# Clock_circuit.net
KiCad netlist of a schematic drawn in Altium Designer
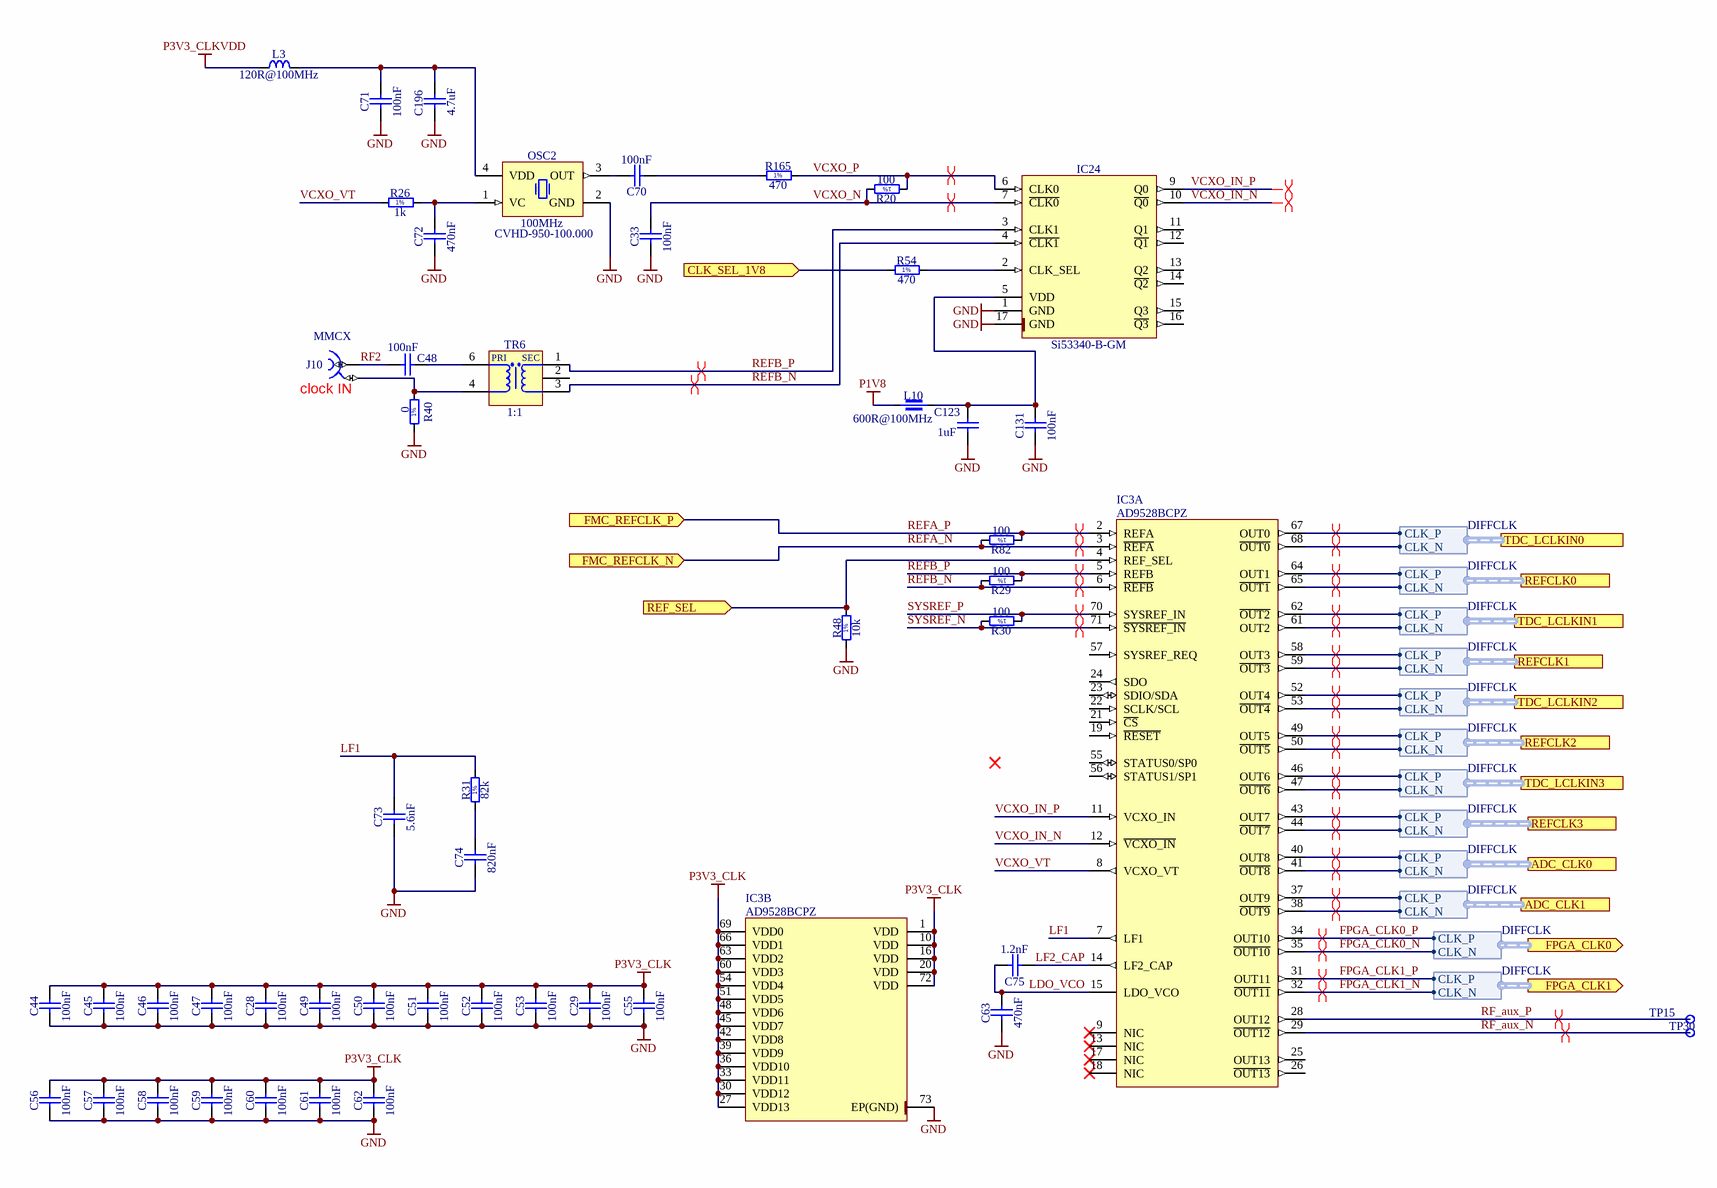
[diagram p0: Clock_circuit.SchDoc]

(export (version "E")
  (design (tool "Eeschema 10.0.6"))
  (components
    (comp (ref "C28")
      (value "100nF")
      (footprint "CAPC0603X33N")
      (description "Non-polarised capacitor")
      (fields
        (field (name "TOLERANCE") "±10%")
        (field (name "PART NUMBER") "CC0201_100NF_6.3V_10%_X5R")
        (field (name "AUTHOR") "CERN DEM JLC")
      )
      (libsource (lib "Capacitors") (part "Capacitor - non polarized"))
    )
    (comp (ref "C29")
      (value "100nF")
      (footprint "CAPC0603X33N")
      (description "Non-polarised capacitor")
      (fields
        (field (name "TOLERANCE") "±10%")
        (field (name "PART NUMBER") "CC0201_100NF_6.3V_10%_X5R")
        (field (name "AUTHOR") "CERN DEM JLC")
      )
      (libsource (lib "Capacitors") (part "Capacitor - non polarized"))
    )
    (comp (ref "C33")
      (value "100nF")
      (footprint "CAPC0603X33N")
      (description "Non-polarised capacitor")
      (fields
        (field (name "TOLERANCE") "±10%")
        (field (name "PART NUMBER") "CC0201_100NF_6.3V_10%_X5R")
        (field (name "AUTHOR") "CERN DEM JLC")
      )
      (libsource (lib "Capacitors") (part "Capacitor - non polarized"))
    )
    (comp (ref "C44")
      (value "100nF")
      (footprint "CAPC0603X33N")
      (description "Non-polarised capacitor")
      (fields
        (field (name "TOLERANCE") "±10%")
        (field (name "PART NUMBER") "CC0201_100NF_6.3V_10%_X5R")
        (field (name "AUTHOR") "CERN DEM JLC")
      )
      (libsource (lib "Capacitors") (part "Capacitor - non polarized"))
    )
    (comp (ref "C45")
      (value "100nF")
      (footprint "CAPC0603X33N")
      (description "Non-polarised capacitor")
      (fields
        (field (name "TOLERANCE") "±10%")
        (field (name "PART NUMBER") "CC0201_100NF_6.3V_10%_X5R")
        (field (name "AUTHOR") "CERN DEM JLC")
      )
      (libsource (lib "Capacitors") (part "Capacitor - non polarized"))
    )
    (comp (ref "C46")
      (value "100nF")
      (footprint "CAPC0603X33N")
      (description "Non-polarised capacitor")
      (fields
        (field (name "TOLERANCE") "±10%")
        (field (name "PART NUMBER") "CC0201_100NF_6.3V_10%_X5R")
        (field (name "AUTHOR") "CERN DEM JLC")
      )
      (libsource (lib "Capacitors") (part "Capacitor - non polarized"))
    )
    (comp (ref "C47")
      (value "100nF")
      (footprint "CAPC0603X33N")
      (description "Non-polarised capacitor")
      (fields
        (field (name "TOLERANCE") "±10%")
        (field (name "PART NUMBER") "CC0201_100NF_6.3V_10%_X5R")
        (field (name "AUTHOR") "CERN DEM JLC")
      )
      (libsource (lib "Capacitors") (part "Capacitor - non polarized"))
    )
    (comp (ref "C48")
      (value "100nF")
      (footprint "CAPC0603X33N")
      (description "Non-polarised capacitor")
      (fields
        (field (name "PART NUMBER") "CC0201_100NF_6.3V_10%_X5R")
        (field (name "VOLTAGE") "6.3V")
        (field (name "AUTHOR") "CERN DEM JLC")
      )
      (libsource (lib "Capacitors") (part "Capacitor - non polarized"))
    )
    (comp (ref "C49")
      (value "100nF")
      (footprint "CAPC0603X33N")
      (description "Non-polarised capacitor")
      (fields
        (field (name "TOLERANCE") "±10%")
        (field (name "PART NUMBER") "CC0201_100NF_6.3V_10%_X5R")
        (field (name "AUTHOR") "CERN DEM JLC")
      )
      (libsource (lib "Capacitors") (part "Capacitor - non polarized"))
    )
    (comp (ref "C50")
      (value "100nF")
      (footprint "CAPC0603X33N")
      (description "Non-polarised capacitor")
      (fields
        (field (name "TOLERANCE") "±10%")
        (field (name "PART NUMBER") "CC0201_100NF_6.3V_10%_X5R")
        (field (name "AUTHOR") "CERN DEM JLC")
      )
      (libsource (lib "Capacitors") (part "Capacitor - non polarized"))
    )
    (comp (ref "C51")
      (value "100nF")
      (footprint "CAPC0603X33N")
      (description "Non-polarised capacitor")
      (fields
        (field (name "TOLERANCE") "±10%")
        (field (name "PART NUMBER") "CC0201_100NF_6.3V_10%_X5R")
        (field (name "AUTHOR") "CERN DEM JLC")
      )
      (libsource (lib "Capacitors") (part "Capacitor - non polarized"))
    )
    (comp (ref "C52")
      (value "100nF")
      (footprint "CAPC0603X33N")
      (description "Non-polarised capacitor")
      (fields
        (field (name "TOLERANCE") "±10%")
        (field (name "PART NUMBER") "CC0201_100NF_6.3V_10%_X5R")
        (field (name "AUTHOR") "CERN DEM JLC")
      )
      (libsource (lib "Capacitors") (part "Capacitor - non polarized"))
    )
    (comp (ref "C53")
      (value "100nF")
      (footprint "CAPC0603X33N")
      (description "Non-polarised capacitor")
      (fields
        (field (name "TOLERANCE") "±10%")
        (field (name "PART NUMBER") "CC0201_100NF_6.3V_10%_X5R")
        (field (name "AUTHOR") "CERN DEM JLC")
      )
      (libsource (lib "Capacitors") (part "Capacitor - non polarized"))
    )
    (comp (ref "C55")
      (value "100nF")
      (footprint "CAPC0603X33N")
      (description "Non-polarised capacitor")
      (fields
        (field (name "TOLERANCE") "±10%")
        (field (name "PART NUMBER") "CC0201_100NF_6.3V_10%_X5R")
        (field (name "AUTHOR") "CERN DEM JLC")
      )
      (libsource (lib "Capacitors") (part "Capacitor - non polarized"))
    )
    (comp (ref "C56")
      (value "100nF")
      (footprint "CAPC0603X33N")
      (description "Non-polarised capacitor")
      (fields
        (field (name "TOLERANCE") "±10%")
        (field (name "PART NUMBER") "CC0201_100NF_6.3V_10%_X5R")
        (field (name "AUTHOR") "CERN DEM JLC")
      )
      (libsource (lib "Capacitors") (part "Capacitor - non polarized"))
    )
    (comp (ref "C57")
      (value "100nF")
      (footprint "CAPC0603X33N")
      (description "Non-polarised capacitor")
      (fields
        (field (name "TOLERANCE") "±10%")
        (field (name "PART NUMBER") "CC0201_100NF_6.3V_10%_X5R")
        (field (name "AUTHOR") "CERN DEM JLC")
      )
      (libsource (lib "Capacitors") (part "Capacitor - non polarized"))
    )
    (comp (ref "C58")
      (value "100nF")
      (footprint "CAPC0603X33N")
      (description "Non-polarised capacitor")
      (fields
        (field (name "TOLERANCE") "±10%")
        (field (name "PART NUMBER") "CC0201_100NF_6.3V_10%_X5R")
        (field (name "AUTHOR") "CERN DEM JLC")
      )
      (libsource (lib "Capacitors") (part "Capacitor - non polarized"))
    )
    (comp (ref "C59")
      (value "100nF")
      (footprint "CAPC0603X33N")
      (description "Non-polarised capacitor")
      (fields
        (field (name "TOLERANCE") "±10%")
        (field (name "PART NUMBER") "CC0201_100NF_6.3V_10%_X5R")
        (field (name "AUTHOR") "CERN DEM JLC")
      )
      (libsource (lib "Capacitors") (part "Capacitor - non polarized"))
    )
    (comp (ref "C60")
      (value "100nF")
      (footprint "CAPC0603X33N")
      (description "Non-polarised capacitor")
      (fields
        (field (name "TOLERANCE") "±10%")
        (field (name "PART NUMBER") "CC0201_100NF_6.3V_10%_X5R")
        (field (name "AUTHOR") "CERN DEM JLC")
      )
      (libsource (lib "Capacitors") (part "Capacitor - non polarized"))
    )
    (comp (ref "C61")
      (value "100nF")
      (footprint "CAPC0603X33N")
      (description "Non-polarised capacitor")
      (fields
        (field (name "TOLERANCE") "±10%")
        (field (name "PART NUMBER") "CC0201_100NF_6.3V_10%_X5R")
        (field (name "AUTHOR") "CERN DEM JLC")
      )
      (libsource (lib "Capacitors") (part "Capacitor - non polarized"))
    )
    (comp (ref "C62")
      (value "100nF")
      (footprint "CAPC0603X33N")
      (description "Non-polarised capacitor")
      (fields
        (field (name "TOLERANCE") "±10%")
        (field (name "PART NUMBER") "CC0201_100NF_6.3V_10%_X5R")
        (field (name "AUTHOR") "CERN DEM JLC")
      )
      (libsource (lib "Capacitors") (part "Capacitor - non polarized"))
    )
    (comp (ref "C63")
      (value "470nF")
      (footprint "CAPC1005X55N")
      (description "Non-polarised capacitor")
      (fields
        (field (name "TOLERANCE") "±10%")
        (field (name "PART NUMBER") "CC0402_470NF_6.3V_10%_X5R")
        (field (name "AUTHOR") "CERN DEM JLC")
      )
      (libsource (lib "Capacitors") (part "Capacitor - non polarized"))
    )
    (comp (ref "C70")
      (value "100nF")
      (footprint "CAPC0603X33N")
      (description "Non-polarised capacitor")
      (fields
        (field (name "TOLERANCE") "±10%")
        (field (name "PART NUMBER") "CC0201_100NF_6.3V_10%_X5R")
        (field (name "AUTHOR") "CERN DEM JLC")
      )
      (libsource (lib "Capacitors") (part "Capacitor - non polarized"))
    )
    (comp (ref "C71")
      (value "100nF")
      (footprint "CAPC0603X33N")
      (description "Non-polarised capacitor")
      (fields
        (field (name "TOLERANCE") "±10%")
        (field (name "PART NUMBER") "CC0201_100NF_6.3V_10%_X5R")
        (field (name "AUTHOR") "CERN DEM JLC")
      )
      (libsource (lib "Capacitors") (part "Capacitor - non polarized"))
    )
    (comp (ref "C72")
      (value "470nF")
      (footprint "CAPC1005X55N")
      (description "Non-polarised capacitor")
      (fields
        (field (name "TOLERANCE") "±10%")
        (field (name "PART NUMBER") "CC0402_470NF_6.3V_10%_X5R")
        (field (name "AUTHOR") "CERN DEM JLC")
      )
      (libsource (lib "Capacitors") (part "Capacitor - non polarized"))
    )
    (comp (ref "C73")
      (value "5.6nF")
      (footprint "CAPC2012X88N")
      (description "Non-polarised capacitor")
      (fields
        (field (name "PART NUMBER") "CC0805_5.6NF_50V_5%_C0G")
        (field (name "VOLTAGE") "50V")
        (field (name "AUTHOR") "*")
      )
      (libsource (lib "FMC_ADC") (part "CC0805_5.6NF_50V_5%_C0G"))
    )
    (comp (ref "C74")
      (value "820nF")
      (footprint "CAPC3216X130N")
      (description "Non-polarised capacitor")
      (fields (field (name "PART NUMBER") "CC1206_820NF_25V_10%_X7R") (field (name "VOLTAGE") "25V"))
      (libsource (lib "FMC_ADC") (part "CC1206_820NF_25V_10%_X7R"))
    )
    (comp (ref "C75")
      (value "1.2nF")
      (footprint "CAPC1608X80N")
      (description "Non-polarised capacitor")
      (fields
        (field (name "TOLERANCE") "±5%")
        (field (name "PART NUMBER") "CC0603_1.2NF_50V_5%_C0G")
        (field (name "AUTHOR") "*")
      )
      (libsource (lib "FMC_ADC") (part "CC0603_1.2NF_50V_5%_C0G"))
    )
    (comp (ref "C123")
      (value "1uF")
      (footprint "CAPC1005X55N")
      (description "Non-polarised capacitor")
      (fields
        (field (name "PART NUMBER") "CC0402_1UF_16V_10%_X5R")
        (field (name "VOLTAGE") "16V")
        (field (name "AUTHOR") "CERN DEM JLC")
      )
      (libsource (lib "Capacitors") (part "Capacitor - non polarized"))
    )
    (comp (ref "C131")
      (value "100nF")
      (footprint "CAPC0603X33N")
      (description "Non-polarised capacitor")
      (fields
        (field (name "PART NUMBER") "CC0201_100NF_6.3V_10%_X5R")
        (field (name "VOLTAGE") "6.3V")
        (field (name "AUTHOR") "CERN DEM JLC")
      )
      (libsource (lib "Capacitors") (part "Capacitor - non polarized"))
    )
    (comp (ref "C196")
      (value "4.7uF")
      (footprint "CAPC1608X87N")
      (description "Non-polarised capacitor")
      (fields
        (field (name "PART NUMBER") "CC0603_4.7UF_6.3V_10%_X5R")
        (field (name "VOLTAGE") "6.3V")
        (field (name "AUTHOR") "CERN DEM JLC")
      )
      (libsource (lib "Capacitors") (part "Capacitor - non polarized"))
    )
    (comp (ref "IC3")
      (value "AD9528BCPZ")
      (footprint "QFN50P1000X1000X100-73N-S545")
      (description "Clock Generator with 14 LVDS/HSTL Outputs")
      (fields (field (name "MANUFACTURER") "ANALOG DEVICES") (field (name "AUTHOR") "CERN DEM JLC"))
      (libsource (lib "ICs And Semiconductors") (part "AD9528"))
    )
    (comp (ref "IC24")
      (value "Si53340-B-GM")
      (footprint "QFN50P300X300X90-17N-S175")
      (description "Low-Jitter LVDS Fanout Clock Buffers, 10-Output,  Any-Input, Any-Frequency up to 1250MHz")
      (fields (field (name "MANUFACTURER") "SILICON LABS") (field (name "AUTHOR") "CERN DEM MR"))
      (libsource (lib "ICs And Semiconductors") (part "Si53340"))
    )
    (comp (ref "J10")
      (value "Coax_1Female_1Shield")
      (footprint "HUBER-SUHNER_85_MMCX-50-0-1/111 OH")
      (fields
        (field (name "PART NUMBER") "HUBER-SUHNER_85_MMCX-50-0-1/111 OH")
        (field (name "FAMILY") "MMCX")
        (field (name "MANUFACTURER") "HUBER+SUHNER")
        (field (name "MANUFACTURER PART NUMBER") "85_MMCX-50-0-1/111 OH")
        (field (name "AUTHOR") "CERN DEM JLC")
      )
      (libsource (lib "Connectors") (part "Coax_1Female_1Shield"))
    )
    (comp (ref "L3")
      (value "120R@100MHz")
      (footprint "INDC1608X65N")
      (description "Inductor")
      (fields
        (field (name "PART NUMBER") "IND0603_MURATA_BLM18SG121TN1D")
        (field (name "POWER") "3A")
        (field (name "AUTHOR") "CERN DEM JLC")
      )
      (libsource (lib "Inductors & Transformers") (part "Inductor"))
    )
    (comp (ref "L10")
      (value "600R@100MHz")
      (footprint "INDC1005X55N")
      (fields
        (field (name "PART NUMBER") "IND0402_MURATA_BLM15HD601SN1")
        (field (name "POWER") "300mA")
        (field (name "TOLERANCE") "±25%")
        (field (name "AUTHOR") "CERN DEM JLC")
      )
      (libsource (lib "Inductors & Transformers") (part "Ferrite Bead"))
    )
    (comp (ref "OSC2")
      (value "100MHz")
      (footprint "OSC_CRYSTEK_CVHD-950")
      (description "Oscillator 4 pins 1=VC 2=GND 3=OUT 4=VDD")
      (fields
        (field (name "PART NUMBER") "OSC_125MHZ_CRYSTEK_CVHD-950-100.000")
        (field (name "MANUFACTURER") "CRYSTEK CRYSTAL")
        (field (name "MANUFACTURER PART NUMBER") "CVHD-950-100.000")
        (field (name "AUTHOR") "CERN DEM JLC")
      )
      (libsource (lib "ICs And Semiconductors") (part "Oscillator 1VC 2GND 3OUT 4VDD"))
    )
    (comp (ref "R20")
      (value "100")
      (footprint "RESC0603X28N")
      (description "Resistor - 1%")
      (fields
        (field (name "PART NUMBER") "R0201_100R_1%_0.05W_200PPM")
        (field (name "POWER") "0.05W")
        (field (name "AUTHOR") "CERN DEM JLC")
      )
      (libsource (lib "Resistors") (part "Resistor - 1%"))
    )
    (comp (ref "R26")
      (value "1k")
      (footprint "RESC1005X40N")
      (description "Resistor - 1%")
      (fields
        (field (name "TOLERANCE") "±1%")
        (field (name "POWER") "0.0625W")
        (field (name "AUTHOR") "CERN DEM JLC")
      )
      (libsource (lib "Resistors") (part "Resistor - 1%"))
    )
    (comp (ref "R29")
      (value "100")
      (footprint "RESC0603X28N")
      (description "Resistor - 1%")
      (fields
        (field (name "PART NUMBER") "R0201_100R_1%_0.05W_200PPM")
        (field (name "POWER") "0.05W")
        (field (name "AUTHOR") "CERN DEM JLC")
      )
      (libsource (lib "Resistors") (part "Resistor - 1%"))
    )
    (comp (ref "R30")
      (value "100")
      (footprint "RESC0603X28N")
      (description "Resistor - 1%")
      (fields
        (field (name "PART NUMBER") "R0201_100R_1%_0.05W_200PPM")
        (field (name "POWER") "0.05W")
        (field (name "AUTHOR") "CERN DEM JLC")
      )
      (libsource (lib "Resistors") (part "Resistor - 1%"))
    )
    (comp (ref "R31")
      (value "82k")
      (footprint "RESC1005X40N")
      (description "Resistor - 1%")
      (fields
        (field (name "TOLERANCE") "±1%")
        (field (name "POWER") "0.0625W")
        (field (name "AUTHOR") "CERN DEM JLC")
      )
      (libsource (lib "Resistors") (part "Resistor - 1%"))
    )
    (comp (ref "R40")
      (value "0")
      (footprint "RESC1005X40N")
      (description "Resistor - 1%")
      (fields
        (field (name "PART NUMBER") "R0402_0R_JUMPER")
        (field (name "MANUFACTURER") "GENERIC")
        (field (name "AUTHOR") "CERN DEM JLC")
      )
      (libsource (lib "Resistors") (part "Resistor - 1%"))
    )
    (comp (ref "R48")
      (value "10k")
      (footprint "RESC1005X40N")
      (description "Resistor - 1%")
      (fields
        (field (name "PART NUMBER") "R0402_10K_1%_0.0625W_100PPM")
        (field (name "POWER") "0.0625W")
        (field (name "AUTHOR") "CERN DEM JLC")
      )
      (libsource (lib "Resistors") (part "Resistor - 1%"))
    )
    (comp (ref "R54")
      (value "470")
      (footprint "RESC1005X40N")
      (description "Resistor - 1%")
      (fields
        (field (name "PART NUMBER") "R0402_470R_1%_0.0625W_100PPM")
        (field (name "POWER") "0.0625W")
        (field (name "AUTHOR") "CERN DEM JLC")
      )
      (libsource (lib "Resistors") (part "Resistor - 1%"))
    )
    (comp (ref "R82")
      (value "100")
      (footprint "RESC0603X28N")
      (description "Resistor - 1%")
      (fields
        (field (name "PART NUMBER") "R0201_100R_1%_0.05W_200PPM")
        (field (name "POWER") "0.05W")
        (field (name "AUTHOR") "CERN DEM JLC")
      )
      (libsource (lib "Resistors") (part "Resistor - 1%"))
    )
    (comp (ref "R165")
      (value "470")
      (footprint "RESC1005X40N")
      (description "Resistor - 1%")
      (fields
        (field (name "PART NUMBER") "R0402_470R_1%_0.0625W_100PPM")
        (field (name "POWER") "0.0625W")
        (field (name "AUTHOR") "CERN DEM JLC")
      )
      (libsource (lib "Resistors") (part "Resistor - 1%"))
    )
    (comp (ref "TP15")
      (value "Test Point")
      (footprint "TPS62")
      (fields (field (name "PART NUMBER") "SMD_PAD_0.62X0.62MM") (field (name "AUTHOR") "CERN DEM JLC"))
      (libsource (lib "FMC_ADC") (part "Test Point"))
    )
    (comp (ref "TP30")
      (value "Test Point")
      (footprint "TPS62")
      (fields (field (name "PART NUMBER") "SMD_PAD_0.62X0.62MM") (field (name "AUTHOR") "CERN DEM JLC"))
      (libsource (lib "FMC_ADC") (part "Test Point"))
    )
    (comp (ref "TR6")
      (value "1:1")
      (footprint "XFMR_MINI-CIRCUITS_AT224-1")
      (description "50 Ohm  0.4 To 500MHz RF Transformers")
      (fields
        (field (name "PART NUMBER") "XFMR_MINI-CIRCUITS_TC1-1T+")
        (field (name "MANUFACTURER") "MINI-CIRCUITS")
        (field (name "AUTHOR") "CERN DEM JLC")
      )
      (libsource (lib "Inductors & Transformers") (part "XFMR_MINI-CIRCUITS_TC1-1+"))
    )
  )
  (nets
    (net (code "2") (name "/CLK_SEL_1V8") (class "Default")
      (node (ref "R54") (pin "1") (pinfunction "1_1") (pintype "passive"))
    )
    (net (code "3") (name "/FPGA_CLK0_N") (class "Default")
      (node (ref "IC3") (pin "35") (pinfunction "~{OUT10}_35") (pintype "output"))
    )
    (net (code "4") (name "/FPGA_CLK0_P") (class "Default")
      (node (ref "IC3") (pin "34") (pinfunction "OUT10_34") (pintype "output"))
    )
    (net (code "5") (name "/FPGA_CLK1_N") (class "Default")
      (node (ref "IC3") (pin "32") (pinfunction "~{OUT11}_32") (pintype "output"))
    )
    (net (code "6") (name "/FPGA_CLK1_P") (class "Default")
      (node (ref "IC3") (pin "31") (pinfunction "OUT11_31") (pintype "output"))
    )
    (net (code "7") (name "/LDO_VCO") (class "Default")
      (node (ref "C63") (pin "2") (pinfunction "2_2") (pintype "passive"))
      (node (ref "C75") (pin "2") (pinfunction "2_2") (pintype "passive"))
      (node (ref "IC3") (pin "15") (pinfunction "LDO_VCO_15") (pintype "power_in"))
    )
    (net (code "8") (name "/LF1") (class "Default")
      (node (ref "C73") (pin "2") (pinfunction "2_2") (pintype "passive"))
      (node (ref "IC3") (pin "7") (pinfunction "LF1_7") (pintype "output"))
      (node (ref "R31") (pin "2") (pinfunction "2_2") (pintype "passive"))
    )
    (net (code "9") (name "/LF2_CAP") (class "Default")
      (node (ref "C75") (pin "1") (pinfunction "1_1") (pintype "passive"))
      (node (ref "IC3") (pin "14") (pinfunction "LF2_CAP_14") (pintype "output"))
    )
    (net (code "10") (name "/REFA_N") (class "Default")
      (node (ref "IC3") (pin "3") (pinfunction "~{REFA}_3") (pintype "input"))
      (node (ref "R82") (pin "2") (pinfunction "2_2") (pintype "passive"))
    )
    (net (code "11") (name "/REFA_P") (class "Default")
      (node (ref "IC3") (pin "2") (pinfunction "REFA_2") (pintype "input"))
      (node (ref "R82") (pin "1") (pinfunction "1_1") (pintype "passive"))
    )
    (net (code "12") (name "/REFB_N") (class "Default")
      (node (ref "IC24") (pin "4") (pinfunction "~{CLK1}_4") (pintype "input"))
      (node (ref "IC3") (pin "6") (pinfunction "~{REFB}_6") (pintype "input"))
      (node (ref "R29") (pin "2") (pinfunction "2_2") (pintype "passive"))
      (node (ref "TR6") (pin "3") (pinfunction "S_3") (pintype "passive"))
    )
    (net (code "13") (name "/REFB_P") (class "Default")
      (node (ref "IC24") (pin "3") (pinfunction "CLK1_3") (pintype "input"))
      (node (ref "IC3") (pin "5") (pinfunction "REFB_5") (pintype "input"))
      (node (ref "R29") (pin "1") (pinfunction "1_1") (pintype "passive"))
      (node (ref "TR6") (pin "1") (pinfunction "SDOT_1") (pintype "passive"))
    )
    (net (code "14") (name "/REF_SEL") (class "Default")
      (node (ref "IC3") (pin "4") (pinfunction "REF_SEL_4") (pintype "input"))
      (node (ref "R48") (pin "2") (pinfunction "2_2") (pintype "passive"))
    )
    (net (code "15") (name "/RF2") (class "Default")
      (node (ref "C48") (pin "2") (pinfunction "2_2") (pintype "passive"))
      (node (ref "J10") (pin "1") (pinfunction "1_1") (pintype "bidirectional"))
    )
    (net (code "16") (name "/RF_aux_N") (class "Default")
      (node (ref "IC3") (pin "29") (pinfunction "~{OUT12}_29") (pintype "output"))
      (node (ref "TP30") (pin "1") (pinfunction "1_1") (pintype "bidirectional"))
    )
    (net (code "17") (name "/RF_aux_P") (class "Default")
      (node (ref "IC3") (pin "28") (pinfunction "OUT12_28") (pintype "output"))
      (node (ref "TP15") (pin "1") (pinfunction "1_1") (pintype "bidirectional"))
    )
    (net (code "18") (name "/SYSREF_N") (class "Default")
      (node (ref "IC3") (pin "71") (pinfunction "~{SYSREF_IN}_71") (pintype "input"))
      (node (ref "R30") (pin "2") (pinfunction "2_2") (pintype "passive"))
    )
    (net (code "19") (name "/SYSREF_P") (class "Default")
      (node (ref "IC3") (pin "70") (pinfunction "SYSREF_IN_70") (pintype "input"))
      (node (ref "R30") (pin "1") (pinfunction "1_1") (pintype "passive"))
    )
    (net (code "20") (name "/VCXO_IN_N") (class "Default")
      (node (ref "IC24") (pin "10") (pinfunction "~{Q0}_10") (pintype "output"))
      (node (ref "IC3") (pin "12") (pinfunction "~{VCXO_IN}_12") (pintype "input"))
    )
    (net (code "21") (name "/VCXO_IN_P") (class "Default")
      (node (ref "IC24") (pin "9") (pinfunction "Q0_9") (pintype "output"))
      (node (ref "IC3") (pin "11") (pinfunction "VCXO_IN_11") (pintype "input"))
    )
    (net (code "22") (name "/VCXO_N") (class "Default")
      (node (ref "C33") (pin "2") (pinfunction "2_2") (pintype "passive"))
      (node (ref "IC24") (pin "7") (pinfunction "~{CLK0}_7") (pintype "input"))
      (node (ref "R20") (pin "2") (pinfunction "2_2") (pintype "passive"))
    )
    (net (code "23") (name "/VCXO_P") (class "Default")
      (node (ref "IC24") (pin "6") (pinfunction "CLK0_6") (pintype "input"))
      (node (ref "R165") (pin "2") (pinfunction "2_2") (pintype "passive"))
      (node (ref "R20") (pin "1") (pinfunction "1_1") (pintype "passive"))
    )
    (net (code "24") (name "/VCXO_VT") (class "Default")
      (node (ref "IC3") (pin "8") (pinfunction "VCXO_VT_8") (pintype "output"))
      (node (ref "R26") (pin "1") (pinfunction "1_1") (pintype "passive"))
    )
    (net (code "26") (name "GND") (class "Default")
      (node (ref "C123") (pin "1") (pinfunction "1_1") (pintype "passive"))
      (node (ref "C131") (pin "1") (pinfunction "1_1") (pintype "passive"))
      (node (ref "C196") (pin "1") (pinfunction "1_1") (pintype "passive"))
      (node (ref "C28") (pin "1") (pinfunction "1_1") (pintype "passive"))
      (node (ref "C29") (pin "1") (pinfunction "1_1") (pintype "passive"))
      (node (ref "C33") (pin "1") (pinfunction "1_1") (pintype "passive"))
      (node (ref "C44") (pin "1") (pinfunction "1_1") (pintype "passive"))
      (node (ref "C45") (pin "1") (pinfunction "1_1") (pintype "passive"))
      (node (ref "C46") (pin "1") (pinfunction "1_1") (pintype "passive"))
      (node (ref "C47") (pin "1") (pinfunction "1_1") (pintype "passive"))
      (node (ref "C49") (pin "1") (pinfunction "1_1") (pintype "passive"))
      (node (ref "C50") (pin "1") (pinfunction "1_1") (pintype "passive"))
      (node (ref "C51") (pin "1") (pinfunction "1_1") (pintype "passive"))
      (node (ref "C52") (pin "1") (pinfunction "1_1") (pintype "passive"))
      (node (ref "C53") (pin "1") (pinfunction "1_1") (pintype "passive"))
      (node (ref "C55") (pin "1") (pinfunction "1_1") (pintype "passive"))
      (node (ref "C56") (pin "1") (pinfunction "1_1") (pintype "passive"))
      (node (ref "C57") (pin "1") (pinfunction "1_1") (pintype "passive"))
      (node (ref "C58") (pin "1") (pinfunction "1_1") (pintype "passive"))
      (node (ref "C59") (pin "1") (pinfunction "1_1") (pintype "passive"))
      (node (ref "C60") (pin "1") (pinfunction "1_1") (pintype "passive"))
      (node (ref "C61") (pin "1") (pinfunction "1_1") (pintype "passive"))
      (node (ref "C62") (pin "1") (pinfunction "1_1") (pintype "passive"))
      (node (ref "C63") (pin "1") (pinfunction "1_1") (pintype "passive"))
      (node (ref "C71") (pin "1") (pinfunction "1_1") (pintype "passive"))
      (node (ref "C72") (pin "1") (pinfunction "1_1") (pintype "passive"))
      (node (ref "C73") (pin "1") (pinfunction "1_1") (pintype "passive"))
      (node (ref "C74") (pin "1") (pinfunction "1_1") (pintype "passive"))
      (node (ref "IC24") (pin "1") (pinfunction "GND_1") (pintype "power_in"))
      (node (ref "IC24") (pin "17") (pinfunction "GND_17") (pintype "power_in"))
      (node (ref "IC3") (pin "73") (pinfunction "EP(GND)_73") (pintype "power_in"))
      (node (ref "OSC2") (pin "2") (pinfunction "GND_2") (pintype "power_in"))
      (node (ref "R40") (pin "1") (pinfunction "1_1") (pintype "passive"))
      (node (ref "R48") (pin "1") (pinfunction "1_1") (pintype "passive"))
    )
    (net (code "27") (name "Net-(C70-Pad1)") (class "Default")
      (node (ref "C70") (pin "1") (pinfunction "1_1") (pintype "passive"))
      (node (ref "R165") (pin "1") (pinfunction "1_1") (pintype "passive"))
    )
    (net (code "28") (name "Net-(C74-Pad2)") (class "Default")
      (node (ref "C74") (pin "2") (pinfunction "2_2") (pintype "passive"))
      (node (ref "R31") (pin "1") (pinfunction "1_1") (pintype "passive"))
    )
    (net (code "29") (name "Net-(IC24-CLK_SEL)") (class "Default")
      (node (ref "IC24") (pin "2") (pinfunction "CLK_SEL_2") (pintype "input"))
      (node (ref "R54") (pin "2") (pinfunction "2_2") (pintype "passive"))
    )
    (net (code "30") (name "Net-(IC24-VDD)") (class "Default")
      (node (ref "C123") (pin "2") (pinfunction "2_2") (pintype "passive"))
      (node (ref "C131") (pin "2") (pinfunction "2_2") (pintype "passive"))
      (node (ref "IC24") (pin "5") (pinfunction "VDD_5") (pintype "power_in"))
      (node (ref "L10") (pin "2") (pinfunction "2_2") (pintype "passive"))
    )
    (net (code "31") (name "Net-(OSC2-OUT)") (class "Default")
      (node (ref "C70") (pin "2") (pinfunction "2_2") (pintype "passive"))
      (node (ref "OSC2") (pin "3") (pinfunction "OUT_3") (pintype "output"))
    )
    (net (code "32") (name "Net-(OSC2-VC)") (class "Default")
      (node (ref "C72") (pin "2") (pinfunction "2_2") (pintype "passive"))
      (node (ref "OSC2") (pin "1") (pinfunction "VC_1") (pintype "input"))
      (node (ref "R26") (pin "2") (pinfunction "2_2") (pintype "passive"))
    )
    (net (code "33") (name "Net-(OSC2-VDD)") (class "Default")
      (node (ref "C196") (pin "2") (pinfunction "2_2") (pintype "passive"))
      (node (ref "C71") (pin "2") (pinfunction "2_2") (pintype "passive"))
      (node (ref "L3") (pin "2") (pinfunction "2_2") (pintype "passive"))
      (node (ref "OSC2") (pin "4") (pinfunction "VDD_4") (pintype "power_in"))
    )
    (net (code "34") (name "Net-(TR6-P)") (class "Default")
      (node (ref "J10") (pin "2") (pinfunction "2_2") (pintype "bidirectional"))
      (node (ref "R40") (pin "2") (pinfunction "2_2") (pintype "passive"))
      (node (ref "TR6") (pin "4") (pinfunction "P_4") (pintype "passive"))
    )
    (net (code "35") (name "Net-(TR6-PDOT)") (class "Default")
      (node (ref "C48") (pin "1") (pinfunction "1_1") (pintype "passive"))
      (node (ref "TR6") (pin "6") (pinfunction "PDOT_6") (pintype "passive"))
    )
    (net (code "36") (name "P1V8") (class "Default")
      (node (ref "L10") (pin "1") (pinfunction "1_1") (pintype "passive"))
    )
    (net (code "37") (name "P3V3_CLK") (class "Default")
      (node (ref "C28") (pin "2") (pinfunction "2_2") (pintype "passive"))
      (node (ref "C29") (pin "2") (pinfunction "2_2") (pintype "passive"))
      (node (ref "C44") (pin "2") (pinfunction "2_2") (pintype "passive"))
      (node (ref "C45") (pin "2") (pinfunction "2_2") (pintype "passive"))
      (node (ref "C46") (pin "2") (pinfunction "2_2") (pintype "passive"))
      (node (ref "C47") (pin "2") (pinfunction "2_2") (pintype "passive"))
      (node (ref "C49") (pin "2") (pinfunction "2_2") (pintype "passive"))
      (node (ref "C50") (pin "2") (pinfunction "2_2") (pintype "passive"))
      (node (ref "C51") (pin "2") (pinfunction "2_2") (pintype "passive"))
      (node (ref "C52") (pin "2") (pinfunction "2_2") (pintype "passive"))
      (node (ref "C53") (pin "2") (pinfunction "2_2") (pintype "passive"))
      (node (ref "C55") (pin "2") (pinfunction "2_2") (pintype "passive"))
      (node (ref "C56") (pin "2") (pinfunction "2_2") (pintype "passive"))
      (node (ref "C57") (pin "2") (pinfunction "2_2") (pintype "passive"))
      (node (ref "C58") (pin "2") (pinfunction "2_2") (pintype "passive"))
      (node (ref "C59") (pin "2") (pinfunction "2_2") (pintype "passive"))
      (node (ref "C60") (pin "2") (pinfunction "2_2") (pintype "passive"))
      (node (ref "C61") (pin "2") (pinfunction "2_2") (pintype "passive"))
      (node (ref "C62") (pin "2") (pinfunction "2_2") (pintype "passive"))
      (node (ref "IC3") (pin "1") (pinfunction "VDD_1") (pintype "power_in"))
      (node (ref "IC3") (pin "10") (pinfunction "VDD_10") (pintype "power_in"))
      (node (ref "IC3") (pin "16") (pinfunction "VDD_16") (pintype "power_in"))
      (node (ref "IC3") (pin "20") (pinfunction "VDD_20") (pintype "power_in"))
      (node (ref "IC3") (pin "27") (pinfunction "VDD13_27") (pintype "power_in"))
      (node (ref "IC3") (pin "30") (pinfunction "VDD12_30") (pintype "power_in"))
      (node (ref "IC3") (pin "33") (pinfunction "VDD11_33") (pintype "power_in"))
      (node (ref "IC3") (pin "36") (pinfunction "VDD10_36") (pintype "power_in"))
      (node (ref "IC3") (pin "39") (pinfunction "VDD9_39") (pintype "power_in"))
      (node (ref "IC3") (pin "42") (pinfunction "VDD8_42") (pintype "power_in"))
      (node (ref "IC3") (pin "45") (pinfunction "VDD7_45") (pintype "power_in"))
      (node (ref "IC3") (pin "48") (pinfunction "VDD6_48") (pintype "power_in"))
      (node (ref "IC3") (pin "51") (pinfunction "VDD5_51") (pintype "power_in"))
      (node (ref "IC3") (pin "54") (pinfunction "VDD4_54") (pintype "power_in"))
      (node (ref "IC3") (pin "60") (pinfunction "VDD3_60") (pintype "power_in"))
      (node (ref "IC3") (pin "63") (pinfunction "VDD2_63") (pintype "power_in"))
      (node (ref "IC3") (pin "66") (pinfunction "VDD1_66") (pintype "power_in"))
      (node (ref "IC3") (pin "69") (pinfunction "VDD0_69") (pintype "power_in"))
      (node (ref "IC3") (pin "72") (pinfunction "VDD_72") (pintype "power_in"))
    )
    (net (code "38") (name "P3V3_CLKVDD") (class "Default")
      (node (ref "L3") (pin "1") (pinfunction "1_1") (pintype "passive"))
    )
    (net (code "39") (name "unconnected-(IC3A-NIC-Pad9)") (class "Default")
      (node (ref "IC3") (pin "9") (pinfunction "NIC_9") (pintype "passive+no_connect"))
    )
    (net (code "40") (name "unconnected-(IC3A-NIC-Pad13)") (class "Default")
      (node (ref "IC3") (pin "13") (pinfunction "NIC_13") (pintype "passive+no_connect"))
    )
    (net (code "41") (name "unconnected-(IC3A-NIC-Pad17)") (class "Default")
      (node (ref "IC3") (pin "17") (pinfunction "NIC_17") (pintype "passive+no_connect"))
    )
    (net (code "42") (name "unconnected-(IC3A-NIC-Pad18)") (class "Default")
      (node (ref "IC3") (pin "18") (pinfunction "NIC_18") (pintype "passive+no_connect"))
    )
    (net (code "43") (name "unconnected-(IC3A-OUT0-Pad67)") (class "Default")
      (node (ref "IC3") (pin "67") (pinfunction "OUT0_67") (pintype "output"))
    )
    (net (code "44") (name "unconnected-(IC3A-OUT1-Pad64)") (class "Default")
      (node (ref "IC3") (pin "64") (pinfunction "OUT1_64") (pintype "output"))
    )
    (net (code "45") (name "unconnected-(IC3A-OUT2-Pad61)") (class "Default")
      (node (ref "IC3") (pin "61") (pinfunction "OUT2_61") (pintype "output"))
    )
    (net (code "46") (name "unconnected-(IC3A-OUT3-Pad58)") (class "Default")
      (node (ref "IC3") (pin "58") (pinfunction "OUT3_58") (pintype "output"))
    )
    (net (code "47") (name "unconnected-(IC3A-OUT4-Pad52)") (class "Default")
      (node (ref "IC3") (pin "52") (pinfunction "OUT4_52") (pintype "output"))
    )
    (net (code "48") (name "unconnected-(IC3A-OUT5-Pad49)") (class "Default")
      (node (ref "IC3") (pin "49") (pinfunction "OUT5_49") (pintype "output"))
    )
    (net (code "49") (name "unconnected-(IC3A-OUT6-Pad46)") (class "Default")
      (node (ref "IC3") (pin "46") (pinfunction "OUT6_46") (pintype "output"))
    )
    (net (code "50") (name "unconnected-(IC3A-OUT7-Pad43)") (class "Default")
      (node (ref "IC3") (pin "43") (pinfunction "OUT7_43") (pintype "output"))
    )
    (net (code "51") (name "unconnected-(IC3A-OUT8-Pad40)") (class "Default")
      (node (ref "IC3") (pin "40") (pinfunction "OUT8_40") (pintype "output"))
    )
    (net (code "52") (name "unconnected-(IC3A-OUT9-Pad37)") (class "Default")
      (node (ref "IC3") (pin "37") (pinfunction "OUT9_37") (pintype "output"))
    )
    (net (code "53") (name "unconnected-(IC3A-OUT13-Pad25)") (class "Default")
      (node (ref "IC3") (pin "25") (pinfunction "OUT13_25") (pintype "output"))
    )
    (net (code "54") (name "unconnected-(IC3A-SCLK{slash}SCL-Pad22)") (class "Default")
      (node (ref "IC3") (pin "22") (pinfunction "SCLK/SCL_22") (pintype "input"))
    )
    (net (code "55") (name "unconnected-(IC3A-SDIO{slash}SDA-Pad23)") (class "Default")
      (node (ref "IC3") (pin "23") (pinfunction "SDIO/SDA_23") (pintype "bidirectional"))
    )
    (net (code "56") (name "unconnected-(IC3A-SDO-Pad24)") (class "Default")
      (node (ref "IC3") (pin "24") (pinfunction "SDO_24") (pintype "output"))
    )
    (net (code "57") (name "unconnected-(IC3A-STATUS0{slash}SP0-Pad55)") (class "Default")
      (node (ref "IC3") (pin "55") (pinfunction "STATUS0/SP0_55") (pintype "bidirectional"))
    )
    (net (code "58") (name "unconnected-(IC3A-STATUS1{slash}SP1-Pad56)") (class "Default")
      (node (ref "IC3") (pin "56") (pinfunction "STATUS1/SP1_56") (pintype "bidirectional"))
    )
    (net (code "59") (name "unconnected-(IC3A-SYSREF_REQ-Pad57)") (class "Default")
      (node (ref "IC3") (pin "57") (pinfunction "SYSREF_REQ_57") (pintype "input"))
    )
    (net (code "60") (name "unconnected-(IC3A-~{CS}-Pad21)") (class "Default")
      (node (ref "IC3") (pin "21") (pinfunction "~{CS}_21") (pintype "input"))
    )
    (net (code "61") (name "unconnected-(IC3A-~{OUT0}-Pad68)") (class "Default")
      (node (ref "IC3") (pin "68") (pinfunction "~{OUT0}_68") (pintype "output"))
    )
    (net (code "62") (name "unconnected-(IC3A-~{OUT1}-Pad65)") (class "Default")
      (node (ref "IC3") (pin "65") (pinfunction "~{OUT1}_65") (pintype "output"))
    )
    (net (code "63") (name "unconnected-(IC3A-~{OUT2}-Pad62)") (class "Default")
      (node (ref "IC3") (pin "62") (pinfunction "~{OUT2}_62") (pintype "output"))
    )
    (net (code "64") (name "unconnected-(IC3A-~{OUT3}-Pad59)") (class "Default")
      (node (ref "IC3") (pin "59") (pinfunction "~{OUT3}_59") (pintype "output"))
    )
    (net (code "65") (name "unconnected-(IC3A-~{OUT4}-Pad53)") (class "Default")
      (node (ref "IC3") (pin "53") (pinfunction "~{OUT4}_53") (pintype "output"))
    )
    (net (code "66") (name "unconnected-(IC3A-~{OUT5}-Pad50)") (class "Default")
      (node (ref "IC3") (pin "50") (pinfunction "~{OUT5}_50") (pintype "output"))
    )
    (net (code "67") (name "unconnected-(IC3A-~{OUT6}-Pad47)") (class "Default")
      (node (ref "IC3") (pin "47") (pinfunction "~{OUT6}_47") (pintype "output"))
    )
    (net (code "68") (name "unconnected-(IC3A-~{OUT7}-Pad44)") (class "Default")
      (node (ref "IC3") (pin "44") (pinfunction "~{OUT7}_44") (pintype "output"))
    )
    (net (code "69") (name "unconnected-(IC3A-~{OUT8}-Pad41)") (class "Default")
      (node (ref "IC3") (pin "41") (pinfunction "~{OUT8}_41") (pintype "output"))
    )
    (net (code "70") (name "unconnected-(IC3A-~{OUT9}-Pad38)") (class "Default")
      (node (ref "IC3") (pin "38") (pinfunction "~{OUT9}_38") (pintype "output"))
    )
    (net (code "71") (name "unconnected-(IC3A-~{OUT13}-Pad26)") (class "Default")
      (node (ref "IC3") (pin "26") (pinfunction "~{OUT13}_26") (pintype "output"))
    )
    (net (code "72") (name "unconnected-(IC3A-~{RESET}-Pad19)") (class "Default")
      (node (ref "IC3") (pin "19") (pinfunction "~{RESET}_19") (pintype "input"))
    )
    (net (code "73") (name "unconnected-(IC24-Q1-Pad11)") (class "Default")
      (node (ref "IC24") (pin "11") (pinfunction "Q1_11") (pintype "output"))
    )
    (net (code "74") (name "unconnected-(IC24-Q2-Pad13)") (class "Default")
      (node (ref "IC24") (pin "13") (pinfunction "Q2_13") (pintype "output"))
    )
    (net (code "75") (name "unconnected-(IC24-Q3-Pad15)") (class "Default")
      (node (ref "IC24") (pin "15") (pinfunction "Q3_15") (pintype "output"))
    )
    (net (code "76") (name "unconnected-(IC24-~{Q1}-Pad12)") (class "Default")
      (node (ref "IC24") (pin "12") (pinfunction "~{Q1}_12") (pintype "output"))
    )
    (net (code "77") (name "unconnected-(IC24-~{Q2}-Pad14)") (class "Default")
      (node (ref "IC24") (pin "14") (pinfunction "~{Q2}_14") (pintype "output"))
    )
    (net (code "78") (name "unconnected-(IC24-~{Q3}-Pad16)") (class "Default")
      (node (ref "IC24") (pin "16") (pinfunction "~{Q3}_16") (pintype "output"))
    )
    (net (code "79") (name "unconnected-(TR6-NU-Pad2)") (class "Default")
      (node (ref "TR6") (pin "2") (pinfunction "NU_2") (pintype "passive"))
    )
  )
)
